# LIDAR_Motorsteuerung.net
KiCad netlist of a schematic drawn in EAGLE
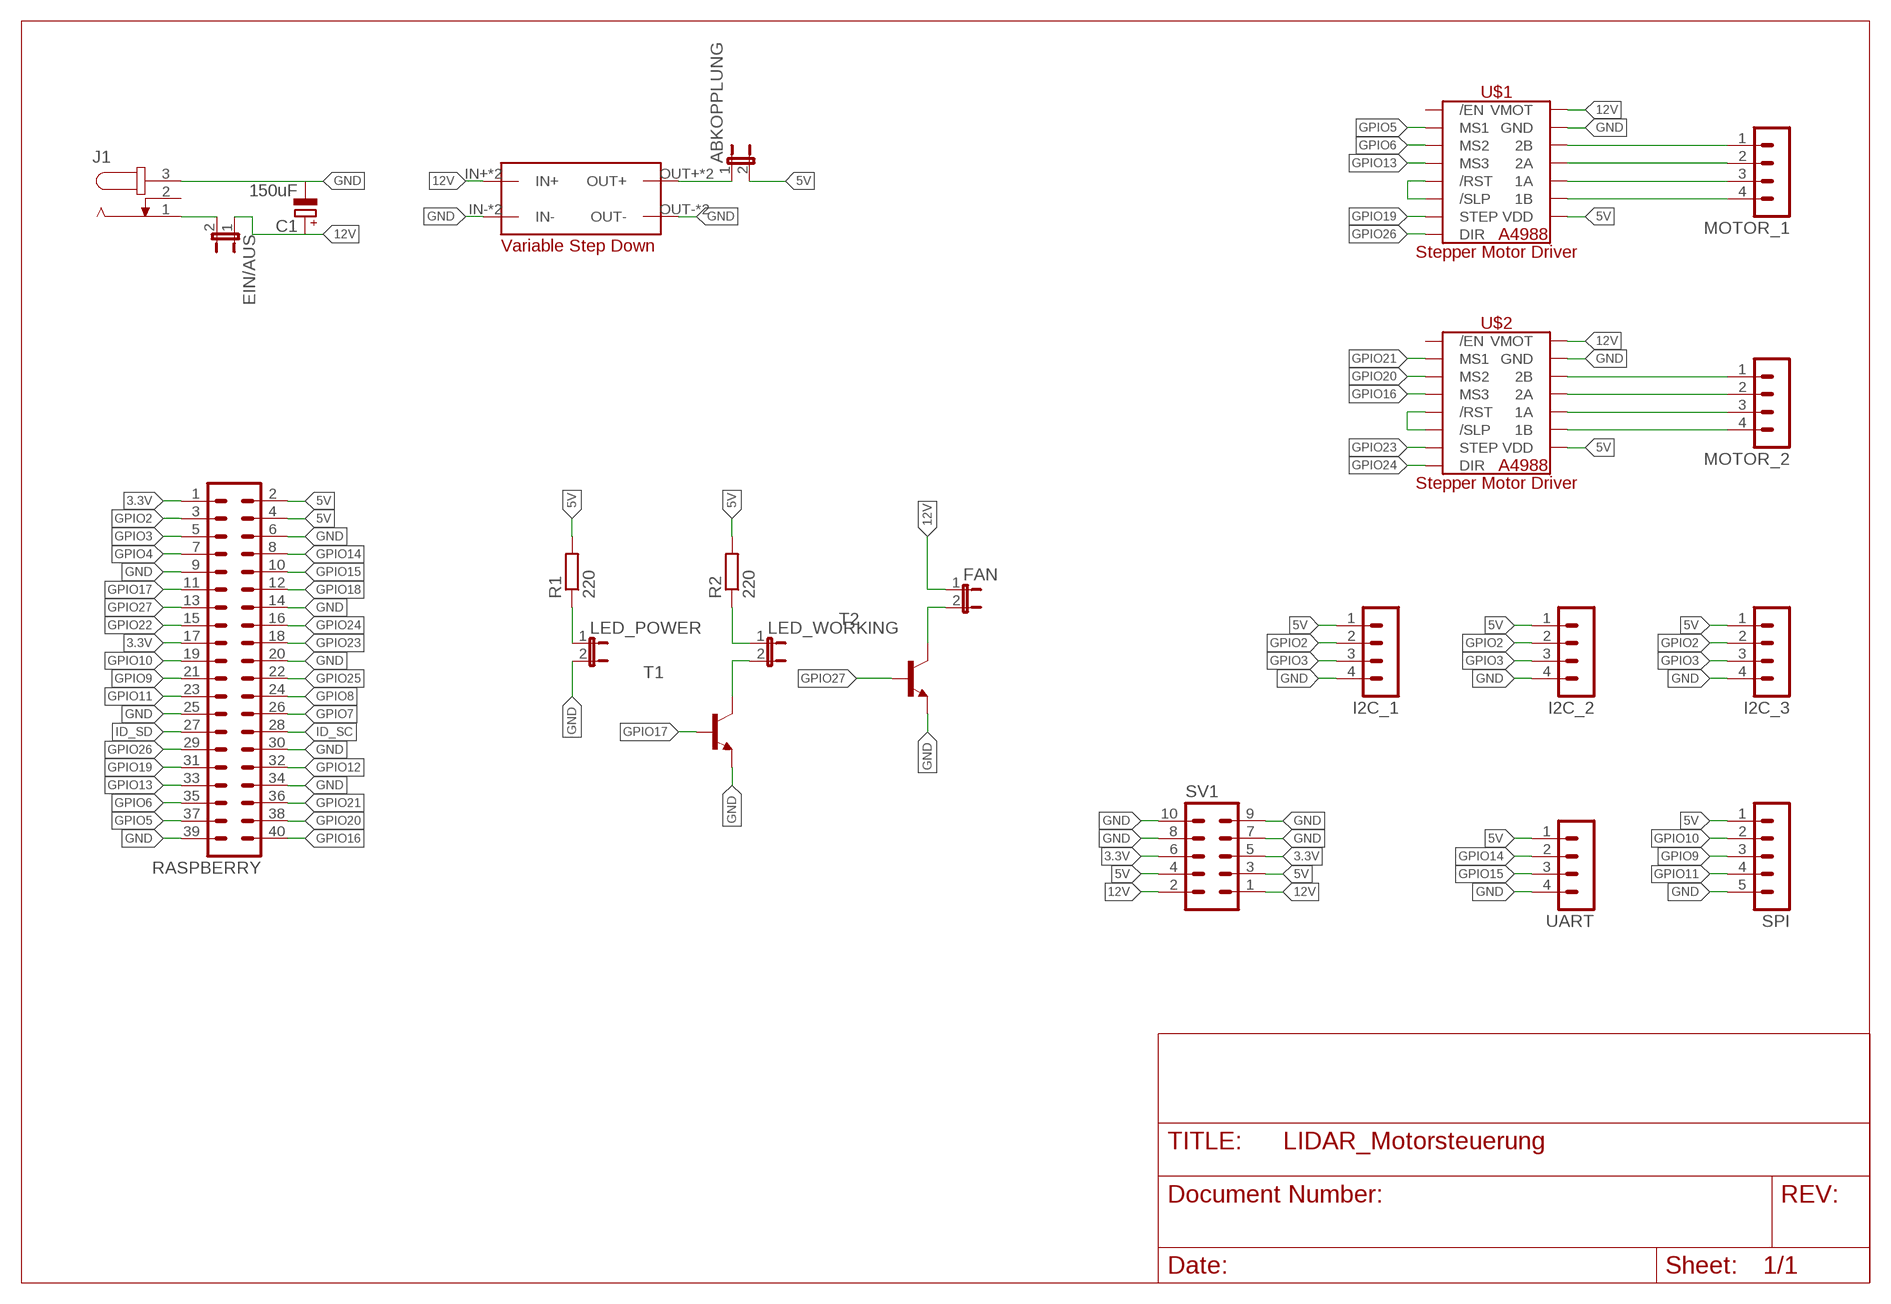
[diagram p0: schematic, sheet 1]

(export (version "E")
  (design (tool "Eeschema 10.0.6"))
  (components
    (comp (ref "ABKOPPLUNG")
      (value "JP1E")
      (footprint "eagle-import:JP1")
      (libsource (lib "eagle-import") (part "JP1E"))
    )
    (comp (ref "C1")
      (value "150uF")
      (footprint "eagle-import:E5-10,5")
      (libsource (lib "eagle-import") (part "CPOL-EUE5-10.5"))
    )
    (comp (ref "EIN/AUS")
      (value "JP1E")
      (footprint "eagle-import:JP1")
      (libsource (lib "eagle-import") (part "JP1E"))
    )
    (comp (ref "FAN")
      (value "JP1E")
      (footprint "eagle-import:JP1")
      (libsource (lib "eagle-import") (part "JP1E"))
    )
    (comp (ref "I2C_1")
      (value "MA04-1")
      (footprint "eagle-import:MA04-1")
      (libsource (lib "eagle-import") (part "MA04-1"))
    )
    (comp (ref "I2C_2")
      (value "MA04-1")
      (footprint "eagle-import:MA04-1")
      (libsource (lib "eagle-import") (part "MA04-1"))
    )
    (comp (ref "I2C_3")
      (value "MA04-1")
      (footprint "eagle-import:MA04-1")
      (libsource (lib "eagle-import") (part "MA04-1"))
    )
    (comp (ref "J1")
      (value "JACK-PLUG0")
      (footprint "eagle-import:SPC4077")
      (libsource (lib "eagle-import") (part "JACK-PLUG0"))
    )
    (comp (ref "LED_POWER")
      (value "JP1E")
      (footprint "eagle-import:JP1")
      (libsource (lib "eagle-import") (part "JP1E"))
    )
    (comp (ref "LED_WORKING")
      (value "JP1E")
      (footprint "eagle-import:JP1")
      (libsource (lib "eagle-import") (part "JP1E"))
    )
    (comp (ref "MOTOR_1")
      (value "MA04-1")
      (footprint "eagle-import:MA04-1")
      (libsource (lib "eagle-import") (part "MA04-1"))
    )
    (comp (ref "MOTOR_2")
      (value "MA04-1")
      (footprint "eagle-import:MA04-1")
      (libsource (lib "eagle-import") (part "MA04-1"))
    )
    (comp (ref "R1")
      (value "220")
      (footprint "eagle-import:0207_10")
      (libsource (lib "eagle-import") (part "R-EU_0207/10"))
    )
    (comp (ref "R2")
      (value "220")
      (footprint "eagle-import:0207_10")
      (libsource (lib "eagle-import") (part "R-EU_0207/10"))
    )
    (comp (ref "RASPBERRY")
      (value "MA20-2")
      (footprint "eagle-import:MA20-2")
      (libsource (lib "eagle-import") (part "MA20-2"))
    )
    (comp (ref "SPI")
      (value "MA05-1")
      (footprint "eagle-import:MA05-1")
      (libsource (lib "eagle-import") (part "MA05-1"))
    )
    (comp (ref "SV1")
      (value "MA05-2")
      (footprint "eagle-import:MA05-2")
      (libsource (lib "eagle-import") (part "MA05-2"))
    )
    (comp (ref "T1")
      (value "-NPN-TO92-EBC")
      (footprint "eagle-import:TO92-EBC")
      (libsource (lib "eagle-import") (part "-NPN-TO92-EBC"))
    )
    (comp (ref "T2")
      (value "-NPN-TO92-EBC")
      (footprint "eagle-import:TO92-EBC")
      (libsource (lib "eagle-import") (part "-NPN-TO92-EBC"))
    )
    (comp (ref "U$1")
      (value "A4988_STEP")
      (footprint "eagle-import:A4988_STEP")
      (libsource (lib "eagle-import") (part "A4988_STEP"))
    )
    (comp (ref "U$2")
      (value "A4988_STEP")
      (footprint "eagle-import:A4988_STEP")
      (libsource (lib "eagle-import") (part "A4988_STEP"))
    )
    (comp (ref "U$3")
      (value "STEP_DOWN")
      (footprint "eagle-import:STEP_DOWN")
      (libsource (lib "eagle-import") (part "STEP_DOWN"))
    )
    (comp (ref "UART")
      (value "MA04-1")
      (footprint "eagle-import:MA04-1")
      (libsource (lib "eagle-import") (part "MA04-1"))
    )
  )
  (nets
    (net (code "1") (name "3.3V") (class "Default")
      (node (ref "RASPBERRY") (pin "1") (pinfunction "1_1") (pintype "passive"))
      (node (ref "RASPBERRY") (pin "17") (pinfunction "17_17") (pintype "passive"))
      (node (ref "SV1") (pin "5") (pinfunction "5_5") (pintype "passive"))
      (node (ref "SV1") (pin "6") (pinfunction "6_6") (pintype "passive"))
    )
    (net (code "2") (name "5V") (class "Default")
      (node (ref "ABKOPPLUNG") (pin "2") (pinfunction "2_2") (pintype "passive"))
      (node (ref "I2C_1") (pin "1") (pinfunction "1_1") (pintype "passive"))
      (node (ref "I2C_2") (pin "1") (pinfunction "1_1") (pintype "passive"))
      (node (ref "I2C_3") (pin "1") (pinfunction "1_1") (pintype "passive"))
      (node (ref "R1") (pin "2") (pinfunction "2_2") (pintype "passive"))
      (node (ref "R2") (pin "2") (pinfunction "2_2") (pintype "passive"))
      (node (ref "RASPBERRY") (pin "2") (pinfunction "2_2") (pintype "passive"))
      (node (ref "RASPBERRY") (pin "4") (pinfunction "4_4") (pintype "passive"))
      (node (ref "SPI") (pin "1") (pinfunction "1_1") (pintype "passive"))
      (node (ref "SV1") (pin "3") (pinfunction "3_3") (pintype "passive"))
      (node (ref "SV1") (pin "4") (pinfunction "4_4") (pintype "passive"))
      (node (ref "U$1") (pin "VDD") (pinfunction "VDD_VDD") (pintype "bidirectional"))
      (node (ref "U$2") (pin "VDD") (pinfunction "VDD_VDD") (pintype "bidirectional"))
      (node (ref "UART") (pin "1") (pinfunction "1_1") (pintype "passive"))
    )
    (net (code "3") (name "12V") (class "Default")
      (node (ref "C1") (pin "+") (pinfunction "+_+") (pintype "passive"))
      (node (ref "EIN/AUS") (pin "1") (pinfunction "1_1") (pintype "passive"))
      (node (ref "FAN") (pin "1") (pinfunction "1_1") (pintype "passive"))
      (node (ref "SV1") (pin "1") (pinfunction "1_1") (pintype "passive"))
      (node (ref "SV1") (pin "2") (pinfunction "2_2") (pintype "passive"))
      (node (ref "U$1") (pin "VMOT") (pinfunction "VMOT_VMOT") (pintype "bidirectional"))
      (node (ref "U$2") (pin "VMOT") (pinfunction "VMOT_VMOT") (pintype "bidirectional"))
      (node (ref "U$3") (pin "IN+") (pinfunction "IN+_IN+") (pintype "bidirectional"))
      (node (ref "U$3") (pin "IN+2") (pinfunction "IN+_IN+2") (pintype "bidirectional"))
    )
    (net (code "4") (name "GND") (class "Default")
      (node (ref "C1") (pin "-") (pinfunction "-_-") (pintype "passive"))
      (node (ref "I2C_1") (pin "4") (pinfunction "4_4") (pintype "passive"))
      (node (ref "I2C_2") (pin "4") (pinfunction "4_4") (pintype "passive"))
      (node (ref "I2C_3") (pin "4") (pinfunction "4_4") (pintype "passive"))
      (node (ref "J1") (pin "3") (pinfunction "3_3") (pintype "passive"))
      (node (ref "LED_POWER") (pin "2") (pinfunction "2_2") (pintype "passive"))
      (node (ref "RASPBERRY") (pin "14") (pinfunction "14_14") (pintype "passive"))
      (node (ref "RASPBERRY") (pin "20") (pinfunction "20_20") (pintype "passive"))
      (node (ref "RASPBERRY") (pin "25") (pinfunction "25_25") (pintype "passive"))
      (node (ref "RASPBERRY") (pin "30") (pinfunction "30_30") (pintype "passive"))
      (node (ref "RASPBERRY") (pin "34") (pinfunction "34_34") (pintype "passive"))
      (node (ref "RASPBERRY") (pin "39") (pinfunction "39_39") (pintype "passive"))
      (node (ref "RASPBERRY") (pin "6") (pinfunction "6_6") (pintype "passive"))
      (node (ref "RASPBERRY") (pin "9") (pinfunction "9_9") (pintype "passive"))
      (node (ref "SPI") (pin "5") (pinfunction "5_5") (pintype "passive"))
      (node (ref "SV1") (pin "10") (pinfunction "10_10") (pintype "passive"))
      (node (ref "SV1") (pin "7") (pinfunction "7_7") (pintype "passive"))
      (node (ref "SV1") (pin "8") (pinfunction "8_8") (pintype "passive"))
      (node (ref "SV1") (pin "9") (pinfunction "9_9") (pintype "passive"))
      (node (ref "T1") (pin "E") (pinfunction "E_E") (pintype "passive"))
      (node (ref "T2") (pin "E") (pinfunction "E_E") (pintype "passive"))
      (node (ref "U$1") (pin "GND") (pinfunction "GND_GND") (pintype "bidirectional"))
      (node (ref "U$1") (pin "GND2") (pinfunction "GND_GND2") (pintype "bidirectional"))
      (node (ref "U$2") (pin "GND") (pinfunction "GND_GND") (pintype "bidirectional"))
      (node (ref "U$2") (pin "GND2") (pinfunction "GND_GND2") (pintype "bidirectional"))
      (node (ref "U$3") (pin "IN-") (pinfunction "IN-_IN-") (pintype "bidirectional"))
      (node (ref "U$3") (pin "IN-2") (pinfunction "IN-_IN-2") (pintype "bidirectional"))
      (node (ref "U$3") (pin "OUT-") (pinfunction "OUT-_OUT-") (pintype "bidirectional"))
      (node (ref "U$3") (pin "OUT-2") (pinfunction "OUT-_OUT-2") (pintype "bidirectional"))
      (node (ref "UART") (pin "4") (pinfunction "4_4") (pintype "passive"))
    )
    (net (code "5") (name "GPIO2") (class "Default")
      (node (ref "I2C_1") (pin "2") (pinfunction "2_2") (pintype "passive"))
      (node (ref "I2C_2") (pin "2") (pinfunction "2_2") (pintype "passive"))
      (node (ref "I2C_3") (pin "2") (pinfunction "2_2") (pintype "passive"))
      (node (ref "RASPBERRY") (pin "3") (pinfunction "3_3") (pintype "passive"))
    )
    (net (code "6") (name "GPIO3") (class "Default")
      (node (ref "I2C_1") (pin "3") (pinfunction "3_3") (pintype "passive"))
      (node (ref "I2C_2") (pin "3") (pinfunction "3_3") (pintype "passive"))
      (node (ref "I2C_3") (pin "3") (pinfunction "3_3") (pintype "passive"))
      (node (ref "RASPBERRY") (pin "5") (pinfunction "5_5") (pintype "passive"))
    )
    (net (code "7") (name "GPIO4") (class "Default")
      (node (ref "RASPBERRY") (pin "7") (pinfunction "7_7") (pintype "passive"))
    )
    (net (code "8") (name "GPIO5") (class "Default")
      (node (ref "RASPBERRY") (pin "37") (pinfunction "37_37") (pintype "passive"))
      (node (ref "U$1") (pin "MS1") (pinfunction "MS1_MS1") (pintype "bidirectional"))
    )
    (net (code "9") (name "GPIO6") (class "Default")
      (node (ref "RASPBERRY") (pin "35") (pinfunction "35_35") (pintype "passive"))
      (node (ref "U$1") (pin "MS2") (pinfunction "MS2_MS2") (pintype "bidirectional"))
    )
    (net (code "10") (name "GPIO7") (class "Default")
      (node (ref "RASPBERRY") (pin "26") (pinfunction "26_26") (pintype "passive"))
    )
    (net (code "11") (name "GPIO8") (class "Default")
      (node (ref "RASPBERRY") (pin "24") (pinfunction "24_24") (pintype "passive"))
    )
    (net (code "12") (name "GPIO9") (class "Default")
      (node (ref "RASPBERRY") (pin "21") (pinfunction "21_21") (pintype "passive"))
      (node (ref "SPI") (pin "3") (pinfunction "3_3") (pintype "passive"))
    )
    (net (code "13") (name "GPIO10") (class "Default")
      (node (ref "RASPBERRY") (pin "19") (pinfunction "19_19") (pintype "passive"))
      (node (ref "SPI") (pin "2") (pinfunction "2_2") (pintype "passive"))
    )
    (net (code "14") (name "GPIO11") (class "Default")
      (node (ref "RASPBERRY") (pin "23") (pinfunction "23_23") (pintype "passive"))
      (node (ref "SPI") (pin "4") (pinfunction "4_4") (pintype "passive"))
    )
    (net (code "15") (name "GPIO12") (class "Default")
      (node (ref "RASPBERRY") (pin "32") (pinfunction "32_32") (pintype "passive"))
    )
    (net (code "16") (name "GPIO13") (class "Default")
      (node (ref "RASPBERRY") (pin "33") (pinfunction "33_33") (pintype "passive"))
      (node (ref "U$1") (pin "MS3") (pinfunction "MS3_MS3") (pintype "bidirectional"))
    )
    (net (code "17") (name "GPIO14") (class "Default")
      (node (ref "RASPBERRY") (pin "8") (pinfunction "8_8") (pintype "passive"))
      (node (ref "UART") (pin "2") (pinfunction "2_2") (pintype "passive"))
    )
    (net (code "18") (name "GPIO15") (class "Default")
      (node (ref "RASPBERRY") (pin "10") (pinfunction "10_10") (pintype "passive"))
      (node (ref "UART") (pin "3") (pinfunction "3_3") (pintype "passive"))
    )
    (net (code "19") (name "GPIO16") (class "Default")
      (node (ref "RASPBERRY") (pin "40") (pinfunction "40_40") (pintype "passive"))
      (node (ref "U$2") (pin "MS3") (pinfunction "MS3_MS3") (pintype "bidirectional"))
    )
    (net (code "20") (name "GPIO17") (class "Default")
      (node (ref "RASPBERRY") (pin "11") (pinfunction "11_11") (pintype "passive"))
      (node (ref "T1") (pin "B") (pinfunction "B_B") (pintype "passive"))
    )
    (net (code "21") (name "GPIO18") (class "Default")
      (node (ref "RASPBERRY") (pin "12") (pinfunction "12_12") (pintype "passive"))
    )
    (net (code "22") (name "GPIO19") (class "Default")
      (node (ref "RASPBERRY") (pin "31") (pinfunction "31_31") (pintype "passive"))
      (node (ref "U$1") (pin "STEP") (pinfunction "STEP_STEP") (pintype "bidirectional"))
    )
    (net (code "23") (name "GPIO20") (class "Default")
      (node (ref "RASPBERRY") (pin "38") (pinfunction "38_38") (pintype "passive"))
      (node (ref "U$2") (pin "MS2") (pinfunction "MS2_MS2") (pintype "bidirectional"))
    )
    (net (code "24") (name "GPIO21") (class "Default")
      (node (ref "RASPBERRY") (pin "36") (pinfunction "36_36") (pintype "passive"))
      (node (ref "U$2") (pin "MS1") (pinfunction "MS1_MS1") (pintype "bidirectional"))
    )
    (net (code "25") (name "GPIO22") (class "Default")
      (node (ref "RASPBERRY") (pin "15") (pinfunction "15_15") (pintype "passive"))
    )
    (net (code "26") (name "GPIO23") (class "Default")
      (node (ref "RASPBERRY") (pin "18") (pinfunction "18_18") (pintype "passive"))
      (node (ref "U$2") (pin "STEP") (pinfunction "STEP_STEP") (pintype "bidirectional"))
    )
    (net (code "27") (name "GPIO24") (class "Default")
      (node (ref "RASPBERRY") (pin "16") (pinfunction "16_16") (pintype "passive"))
      (node (ref "U$2") (pin "DIR") (pinfunction "DIR_DIR") (pintype "bidirectional"))
    )
    (net (code "28") (name "GPIO25") (class "Default")
      (node (ref "RASPBERRY") (pin "22") (pinfunction "22_22") (pintype "passive"))
    )
    (net (code "29") (name "GPIO26") (class "Default")
      (node (ref "RASPBERRY") (pin "29") (pinfunction "29_29") (pintype "passive"))
      (node (ref "U$1") (pin "DIR") (pinfunction "DIR_DIR") (pintype "bidirectional"))
    )
    (net (code "30") (name "GPIO27") (class "Default")
      (node (ref "RASPBERRY") (pin "13") (pinfunction "13_13") (pintype "passive"))
      (node (ref "T2") (pin "B") (pinfunction "B_B") (pintype "passive"))
    )
    (net (code "31") (name "ID_SC") (class "Default")
      (node (ref "RASPBERRY") (pin "28") (pinfunction "28_28") (pintype "passive"))
    )
    (net (code "32") (name "ID_SD") (class "Default")
      (node (ref "RASPBERRY") (pin "27") (pinfunction "27_27") (pintype "passive"))
    )
    (net (code "33") (name "Net-(ABKOPPLUNG-Pad1)") (class "Default")
      (node (ref "ABKOPPLUNG") (pin "1") (pinfunction "1_1") (pintype "passive"))
      (node (ref "U$3") (pin "OUT+") (pinfunction "OUT+_OUT+") (pintype "bidirectional"))
      (node (ref "U$3") (pin "OUT+2") (pinfunction "OUT+_OUT+2") (pintype "bidirectional"))
    )
    (net (code "34") (name "Net-(EIN/AUS-Pad2)") (class "Default")
      (node (ref "EIN/AUS") (pin "2") (pinfunction "2_2") (pintype "passive"))
      (node (ref "J1") (pin "1") (pinfunction "1_1") (pintype "passive"))
    )
    (net (code "35") (name "Net-(FAN-Pad2)") (class "Default")
      (node (ref "FAN") (pin "2") (pinfunction "2_2") (pintype "passive"))
      (node (ref "T2") (pin "C") (pinfunction "C_C") (pintype "passive"))
    )
    (net (code "36") (name "Net-(LED_POWER-Pad1)") (class "Default")
      (node (ref "LED_POWER") (pin "1") (pinfunction "1_1") (pintype "passive"))
      (node (ref "R1") (pin "1") (pinfunction "1_1") (pintype "passive"))
    )
    (net (code "37") (name "Net-(LED_WORKING-Pad1)") (class "Default")
      (node (ref "LED_WORKING") (pin "1") (pinfunction "1_1") (pintype "passive"))
      (node (ref "R2") (pin "1") (pinfunction "1_1") (pintype "passive"))
    )
    (net (code "38") (name "Net-(LED_WORKING-Pad2)") (class "Default")
      (node (ref "LED_WORKING") (pin "2") (pinfunction "2_2") (pintype "passive"))
      (node (ref "T1") (pin "C") (pinfunction "C_C") (pintype "passive"))
    )
    (net (code "39") (name "Net-(MOTOR_1-Pad1)") (class "Default")
      (node (ref "MOTOR_1") (pin "1") (pinfunction "1_1") (pintype "passive"))
      (node (ref "U$1") (pin "2B") (pinfunction "2B_2B") (pintype "bidirectional"))
    )
    (net (code "40") (name "Net-(MOTOR_1-Pad2)") (class "Default")
      (node (ref "MOTOR_1") (pin "2") (pinfunction "2_2") (pintype "passive"))
      (node (ref "U$1") (pin "2A") (pinfunction "2A_2A") (pintype "bidirectional"))
    )
    (net (code "41") (name "Net-(MOTOR_1-Pad3)") (class "Default")
      (node (ref "MOTOR_1") (pin "3") (pinfunction "3_3") (pintype "passive"))
      (node (ref "U$1") (pin "1A") (pinfunction "1A_1A") (pintype "bidirectional"))
    )
    (net (code "42") (name "Net-(MOTOR_1-Pad4)") (class "Default")
      (node (ref "MOTOR_1") (pin "4") (pinfunction "4_4") (pintype "passive"))
      (node (ref "U$1") (pin "1B") (pinfunction "1B_1B") (pintype "bidirectional"))
    )
    (net (code "43") (name "Net-(MOTOR_2-Pad1)") (class "Default")
      (node (ref "MOTOR_2") (pin "1") (pinfunction "1_1") (pintype "passive"))
      (node (ref "U$2") (pin "2B") (pinfunction "2B_2B") (pintype "bidirectional"))
    )
    (net (code "44") (name "Net-(MOTOR_2-Pad2)") (class "Default")
      (node (ref "MOTOR_2") (pin "2") (pinfunction "2_2") (pintype "passive"))
      (node (ref "U$2") (pin "2A") (pinfunction "2A_2A") (pintype "bidirectional"))
    )
    (net (code "45") (name "Net-(MOTOR_2-Pad3)") (class "Default")
      (node (ref "MOTOR_2") (pin "3") (pinfunction "3_3") (pintype "passive"))
      (node (ref "U$2") (pin "1A") (pinfunction "1A_1A") (pintype "bidirectional"))
    )
    (net (code "46") (name "Net-(MOTOR_2-Pad4)") (class "Default")
      (node (ref "MOTOR_2") (pin "4") (pinfunction "4_4") (pintype "passive"))
      (node (ref "U$2") (pin "1B") (pinfunction "1B_1B") (pintype "bidirectional"))
    )
    (net (code "47") (name "Net-(U$1-Pad{slash}RST)") (class "Default")
      (node (ref "U$1") (pin "/RST") (pinfunction "/RST_/RST") (pintype "bidirectional"))
      (node (ref "U$1") (pin "/SLP") (pinfunction "/SLP_/SLP") (pintype "bidirectional"))
    )
    (net (code "48") (name "Net-(U$2-Pad{slash}RST)") (class "Default")
      (node (ref "U$2") (pin "/RST") (pinfunction "/RST_/RST") (pintype "bidirectional"))
      (node (ref "U$2") (pin "/SLP") (pinfunction "/SLP_/SLP") (pintype "bidirectional"))
    )
    (net (code "49") (name "unconnected-(J1-Pad2)") (class "Default")
      (node (ref "J1") (pin "2") (pinfunction "2_2") (pintype "passive"))
    )
    (net (code "50") (name "unconnected-(U$1-Pad{slash}EN)") (class "Default")
      (node (ref "U$1") (pin "/EN") (pinfunction "/EN_/EN") (pintype "bidirectional"))
    )
    (net (code "51") (name "unconnected-(U$2-Pad{slash}EN)") (class "Default")
      (node (ref "U$2") (pin "/EN") (pinfunction "/EN_/EN") (pintype "bidirectional"))
    )
  )
)
